# stereomix-back.net
KiCad netlist of a schematic drawn in EAGLE
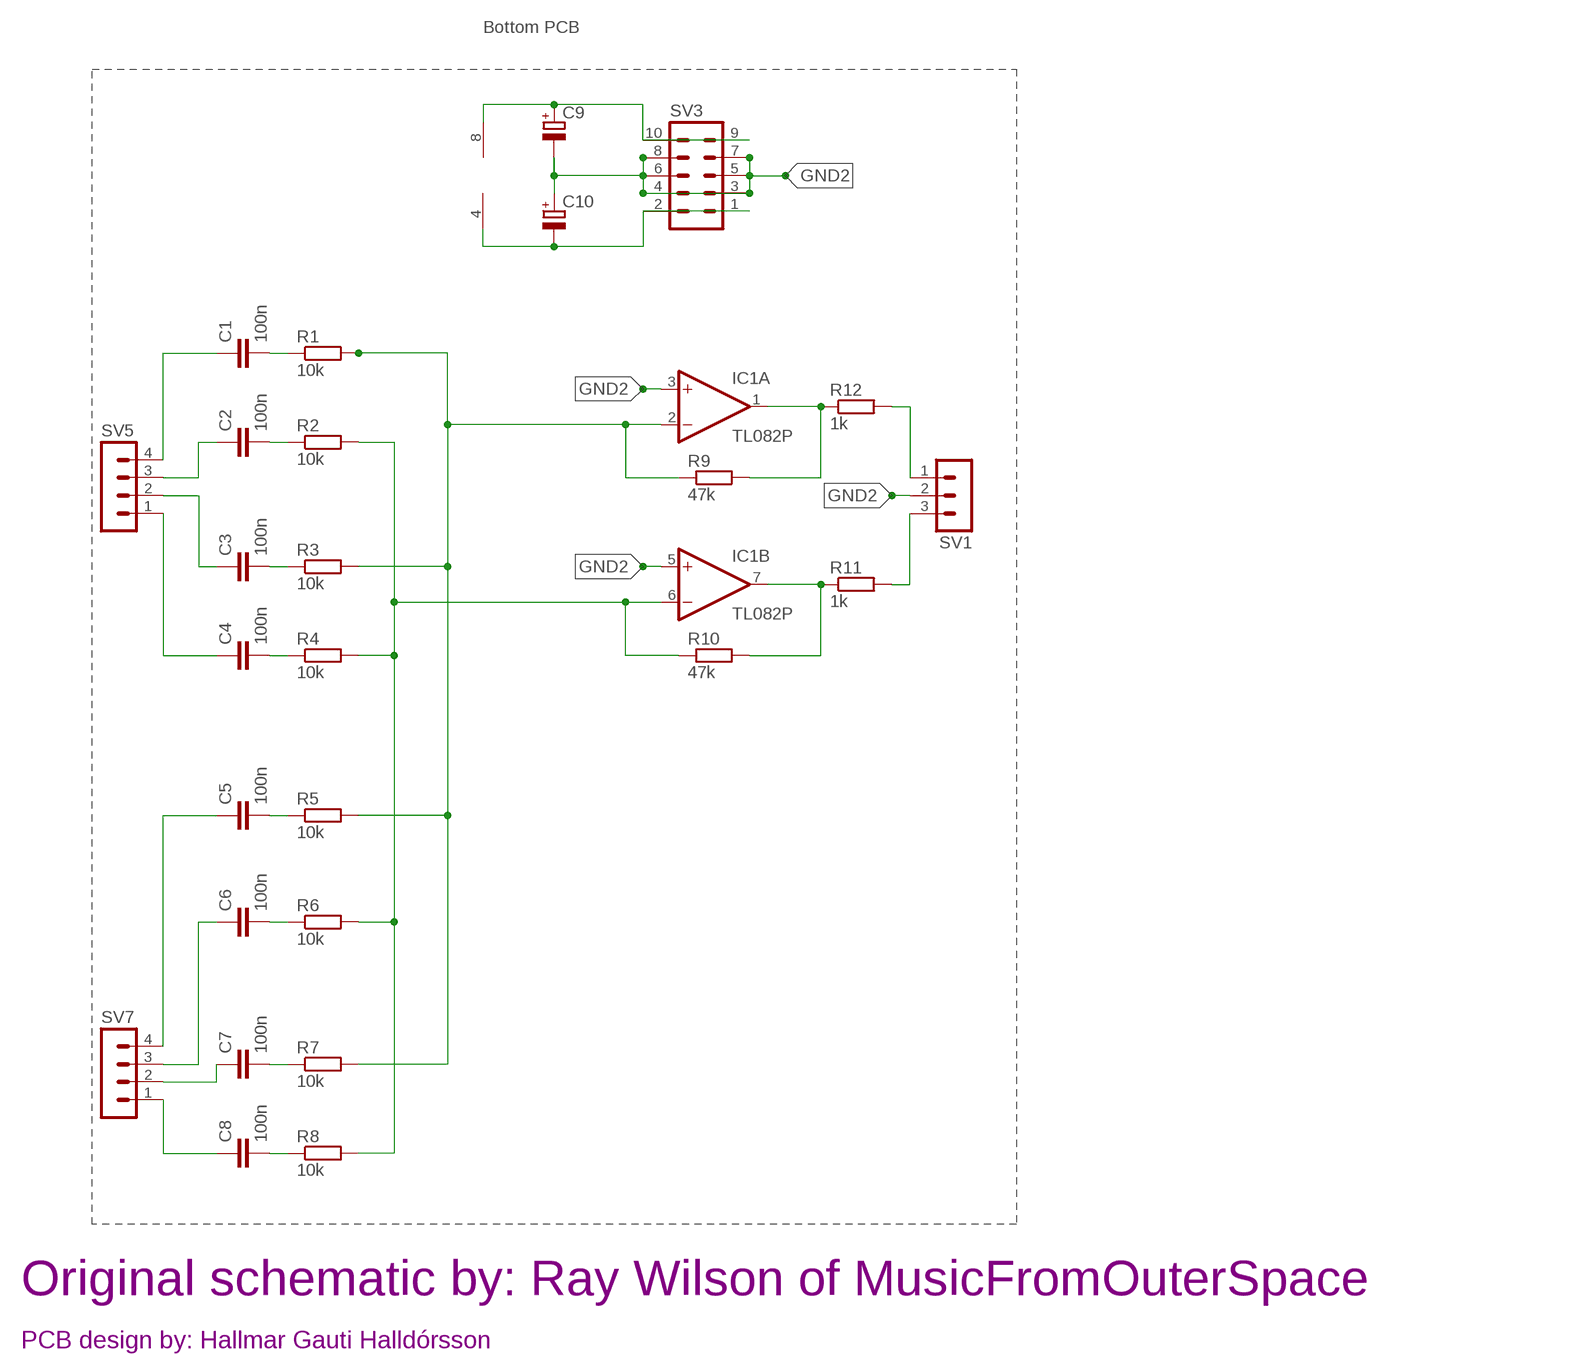
[diagram p0: schematic, sheet 1]

(export (version "E")
  (design (tool "Eeschema 10.0.6"))
  (components
    (comp (ref "C1")
      (value "100n")
      (footprint "eagle-import:C050-024X044")
      (libsource (lib "eagle-import") (part "C-EU050-024X044"))
    )
    (comp (ref "C2")
      (value "100n")
      (footprint "eagle-import:C050-024X044")
      (libsource (lib "eagle-import") (part "C-EU050-024X044"))
    )
    (comp (ref "C3")
      (value "100n")
      (footprint "eagle-import:C050-024X044")
      (libsource (lib "eagle-import") (part "C-EU050-024X044"))
    )
    (comp (ref "C4")
      (value "100n")
      (footprint "eagle-import:C050-024X044")
      (libsource (lib "eagle-import") (part "C-EU050-024X044"))
    )
    (comp (ref "C5")
      (value "100n")
      (footprint "eagle-import:C050-024X044")
      (libsource (lib "eagle-import") (part "C-EU050-024X044"))
    )
    (comp (ref "C6")
      (value "100n")
      (footprint "eagle-import:C050-024X044")
      (libsource (lib "eagle-import") (part "C-EU050-024X044"))
    )
    (comp (ref "C7")
      (value "100n")
      (footprint "eagle-import:C050-024X044")
      (libsource (lib "eagle-import") (part "C-EU050-024X044"))
    )
    (comp (ref "C8")
      (value "100n")
      (footprint "eagle-import:C050-024X044")
      (libsource (lib "eagle-import") (part "C-EU050-024X044"))
    )
    (comp (ref "C9")
      (value "CPOL-EUE2.5-6")
      (footprint "eagle-import:E2,5-6")
      (libsource (lib "eagle-import") (part "CPOL-EUE2.5-6"))
    )
    (comp (ref "C10")
      (value "CPOL-EUE2,5-6E")
      (footprint "eagle-import:E2,5-6E")
      (libsource (lib "eagle-import") (part "CPOL-EUE2,5-6E"))
    )
    (comp (ref "IC1")
      (value "TL082P")
      (footprint "eagle-import:DIL08")
      (libsource (lib "eagle-import") (part "TL082P"))
    )
    (comp (ref "R1")
      (value "10k")
      (footprint "eagle-import:0204_7")
      (libsource (lib "eagle-import") (part "R-EU_0204/7"))
    )
    (comp (ref "R2")
      (value "10k")
      (footprint "eagle-import:0204_7")
      (libsource (lib "eagle-import") (part "R-EU_0204/7"))
    )
    (comp (ref "R3")
      (value "10k")
      (footprint "eagle-import:0204_7")
      (libsource (lib "eagle-import") (part "R-EU_0204/7"))
    )
    (comp (ref "R4")
      (value "10k")
      (footprint "eagle-import:0204_7")
      (libsource (lib "eagle-import") (part "R-EU_0204/7"))
    )
    (comp (ref "R5")
      (value "10k")
      (footprint "eagle-import:0204_7")
      (libsource (lib "eagle-import") (part "R-EU_0204/7"))
    )
    (comp (ref "R6")
      (value "10k")
      (footprint "eagle-import:0204_7")
      (libsource (lib "eagle-import") (part "R-EU_0204/7"))
    )
    (comp (ref "R7")
      (value "10k")
      (footprint "eagle-import:0204_7")
      (libsource (lib "eagle-import") (part "R-EU_0204/7"))
    )
    (comp (ref "R8")
      (value "10k")
      (footprint "eagle-import:0204_7")
      (libsource (lib "eagle-import") (part "R-EU_0204/7"))
    )
    (comp (ref "R9")
      (value "47k")
      (footprint "eagle-import:0204_7")
      (libsource (lib "eagle-import") (part "R-EU_0204/7"))
    )
    (comp (ref "R10")
      (value "47k")
      (footprint "eagle-import:0204_7")
      (libsource (lib "eagle-import") (part "R-EU_0204/7"))
    )
    (comp (ref "R11")
      (value "1k")
      (footprint "eagle-import:0204_7")
      (libsource (lib "eagle-import") (part "R-EU_0204/7"))
    )
    (comp (ref "R12")
      (value "1k")
      (footprint "eagle-import:0204_7")
      (libsource (lib "eagle-import") (part "R-EU_0204/7"))
    )
    (comp (ref "SV1")
      (value "MA03-1")
      (footprint "eagle-import:MA03-1")
      (libsource (lib "eagle-import") (part "MA03-1"))
    )
    (comp (ref "SV3")
      (value "MA05-2")
      (footprint "eagle-import:MA05-2")
      (libsource (lib "eagle-import") (part "MA05-2"))
    )
    (comp (ref "SV5")
      (value "MA04-1")
      (footprint "eagle-import:MA04-1")
      (libsource (lib "eagle-import") (part "MA04-1"))
    )
    (comp (ref "SV7")
      (value "MA04-1")
      (footprint "eagle-import:MA04-1")
      (libsource (lib "eagle-import") (part "MA04-1"))
    )
  )
  (nets
    (net (code "1") (name "GND2") (class "Default")
      (node (ref "C10") (pin "+") (pinfunction "+_+") (pintype "passive"))
      (node (ref "C9") (pin "-") (pinfunction "-_-") (pintype "passive"))
      (node (ref "IC1") (pin "3") (pinfunction "+IN_3") (pintype "input"))
      (node (ref "IC1") (pin "5") (pinfunction "+IN_5") (pintype "input"))
      (node (ref "SV1") (pin "2") (pinfunction "2_2") (pintype "passive"))
      (node (ref "SV3") (pin "3") (pinfunction "3_3") (pintype "passive"))
      (node (ref "SV3") (pin "4") (pinfunction "4_4") (pintype "passive"))
      (node (ref "SV3") (pin "5") (pinfunction "5_5") (pintype "passive"))
      (node (ref "SV3") (pin "6") (pinfunction "6_6") (pintype "passive"))
      (node (ref "SV3") (pin "7") (pinfunction "7_7") (pintype "passive"))
      (node (ref "SV3") (pin "8") (pinfunction "8_8") (pintype "passive"))
    )
    (net (code "2") (name "Net-(C1-Pad1)") (class "Default")
      (node (ref "C1") (pin "1") (pinfunction "1_1") (pintype "passive"))
      (node (ref "SV5") (pin "4") (pinfunction "4_4") (pintype "passive"))
    )
    (net (code "3") (name "Net-(C1-Pad2)") (class "Default")
      (node (ref "C1") (pin "2") (pinfunction "2_2") (pintype "passive"))
      (node (ref "R1") (pin "1") (pinfunction "1_1") (pintype "passive"))
    )
    (net (code "4") (name "Net-(C2-Pad1)") (class "Default")
      (node (ref "C2") (pin "1") (pinfunction "1_1") (pintype "passive"))
      (node (ref "SV5") (pin "3") (pinfunction "3_3") (pintype "passive"))
    )
    (net (code "5") (name "Net-(C2-Pad2)") (class "Default")
      (node (ref "C2") (pin "2") (pinfunction "2_2") (pintype "passive"))
      (node (ref "R2") (pin "1") (pinfunction "1_1") (pintype "passive"))
    )
    (net (code "6") (name "Net-(C3-Pad1)") (class "Default")
      (node (ref "C3") (pin "1") (pinfunction "1_1") (pintype "passive"))
      (node (ref "SV5") (pin "2") (pinfunction "2_2") (pintype "passive"))
    )
    (net (code "7") (name "Net-(C3-Pad2)") (class "Default")
      (node (ref "C3") (pin "2") (pinfunction "2_2") (pintype "passive"))
      (node (ref "R3") (pin "1") (pinfunction "1_1") (pintype "passive"))
    )
    (net (code "8") (name "Net-(C4-Pad1)") (class "Default")
      (node (ref "C4") (pin "1") (pinfunction "1_1") (pintype "passive"))
      (node (ref "SV5") (pin "1") (pinfunction "1_1") (pintype "passive"))
    )
    (net (code "9") (name "Net-(C4-Pad2)") (class "Default")
      (node (ref "C4") (pin "2") (pinfunction "2_2") (pintype "passive"))
      (node (ref "R4") (pin "1") (pinfunction "1_1") (pintype "passive"))
    )
    (net (code "10") (name "Net-(C5-Pad1)") (class "Default")
      (node (ref "C5") (pin "1") (pinfunction "1_1") (pintype "passive"))
      (node (ref "SV7") (pin "4") (pinfunction "4_4") (pintype "passive"))
    )
    (net (code "11") (name "Net-(C5-Pad2)") (class "Default")
      (node (ref "C5") (pin "2") (pinfunction "2_2") (pintype "passive"))
      (node (ref "R5") (pin "1") (pinfunction "1_1") (pintype "passive"))
    )
    (net (code "12") (name "Net-(C6-Pad1)") (class "Default")
      (node (ref "C6") (pin "1") (pinfunction "1_1") (pintype "passive"))
      (node (ref "SV7") (pin "3") (pinfunction "3_3") (pintype "passive"))
    )
    (net (code "13") (name "Net-(C6-Pad2)") (class "Default")
      (node (ref "C6") (pin "2") (pinfunction "2_2") (pintype "passive"))
      (node (ref "R6") (pin "1") (pinfunction "1_1") (pintype "passive"))
    )
    (net (code "14") (name "Net-(C7-Pad1)") (class "Default")
      (node (ref "C7") (pin "1") (pinfunction "1_1") (pintype "passive"))
      (node (ref "SV7") (pin "2") (pinfunction "2_2") (pintype "passive"))
    )
    (net (code "15") (name "Net-(C7-Pad2)") (class "Default")
      (node (ref "C7") (pin "2") (pinfunction "2_2") (pintype "passive"))
      (node (ref "R7") (pin "1") (pinfunction "1_1") (pintype "passive"))
    )
    (net (code "16") (name "Net-(C8-Pad1)") (class "Default")
      (node (ref "C8") (pin "1") (pinfunction "1_1") (pintype "passive"))
      (node (ref "SV7") (pin "1") (pinfunction "1_1") (pintype "passive"))
    )
    (net (code "17") (name "Net-(C8-Pad2)") (class "Default")
      (node (ref "C8") (pin "2") (pinfunction "2_2") (pintype "passive"))
      (node (ref "R8") (pin "1") (pinfunction "1_1") (pintype "passive"))
    )
    (net (code "18") (name "Net-(IC1A--IN)") (class "Default")
      (node (ref "IC1") (pin "2") (pinfunction "-IN_2") (pintype "input"))
      (node (ref "R1") (pin "2") (pinfunction "2_2") (pintype "passive"))
      (node (ref "R3") (pin "2") (pinfunction "2_2") (pintype "passive"))
      (node (ref "R5") (pin "2") (pinfunction "2_2") (pintype "passive"))
      (node (ref "R7") (pin "2") (pinfunction "2_2") (pintype "passive"))
      (node (ref "R9") (pin "1") (pinfunction "1_1") (pintype "passive"))
    )
    (net (code "19") (name "Net-(IC1A-OUT)") (class "Default")
      (node (ref "IC1") (pin "1") (pinfunction "OUT_1") (pintype "output"))
      (node (ref "R12") (pin "1") (pinfunction "1_1") (pintype "passive"))
      (node (ref "R9") (pin "2") (pinfunction "2_2") (pintype "passive"))
    )
    (net (code "20") (name "Net-(IC1B--IN)") (class "Default")
      (node (ref "IC1") (pin "6") (pinfunction "-IN_6") (pintype "input"))
      (node (ref "R10") (pin "1") (pinfunction "1_1") (pintype "passive"))
      (node (ref "R2") (pin "2") (pinfunction "2_2") (pintype "passive"))
      (node (ref "R4") (pin "2") (pinfunction "2_2") (pintype "passive"))
      (node (ref "R6") (pin "2") (pinfunction "2_2") (pintype "passive"))
      (node (ref "R8") (pin "2") (pinfunction "2_2") (pintype "passive"))
    )
    (net (code "21") (name "Net-(IC1B-OUT)") (class "Default")
      (node (ref "IC1") (pin "7") (pinfunction "OUT_7") (pintype "output"))
      (node (ref "R10") (pin "2") (pinfunction "2_2") (pintype "passive"))
      (node (ref "R11") (pin "1") (pinfunction "1_1") (pintype "passive"))
    )
    (net (code "22") (name "Net-(IC1C-V+)") (class "Default")
      (node (ref "C9") (pin "+") (pinfunction "+_+") (pintype "passive"))
      (node (ref "IC1") (pin "8") (pinfunction "V+_8") (pintype "power_in"))
      (node (ref "SV3") (pin "10") (pinfunction "10_10") (pintype "passive"))
      (node (ref "SV3") (pin "9") (pinfunction "9_9") (pintype "passive"))
    )
    (net (code "23") (name "Net-(IC1C-V-)") (class "Default")
      (node (ref "C10") (pin "-") (pinfunction "-_-") (pintype "passive"))
      (node (ref "IC1") (pin "4") (pinfunction "V-_4") (pintype "power_in"))
      (node (ref "SV3") (pin "1") (pinfunction "1_1") (pintype "passive"))
      (node (ref "SV3") (pin "2") (pinfunction "2_2") (pintype "passive"))
    )
    (net (code "24") (name "Net-(R11-Pad2)") (class "Default")
      (node (ref "R11") (pin "2") (pinfunction "2_2") (pintype "passive"))
      (node (ref "SV1") (pin "3") (pinfunction "3_3") (pintype "passive"))
    )
    (net (code "25") (name "Net-(R12-Pad2)") (class "Default")
      (node (ref "R12") (pin "2") (pinfunction "2_2") (pintype "passive"))
      (node (ref "SV1") (pin "1") (pinfunction "1_1") (pintype "passive"))
    )
  )
)
